# MCU.net
KiCad netlist of a schematic drawn in Altium Designer
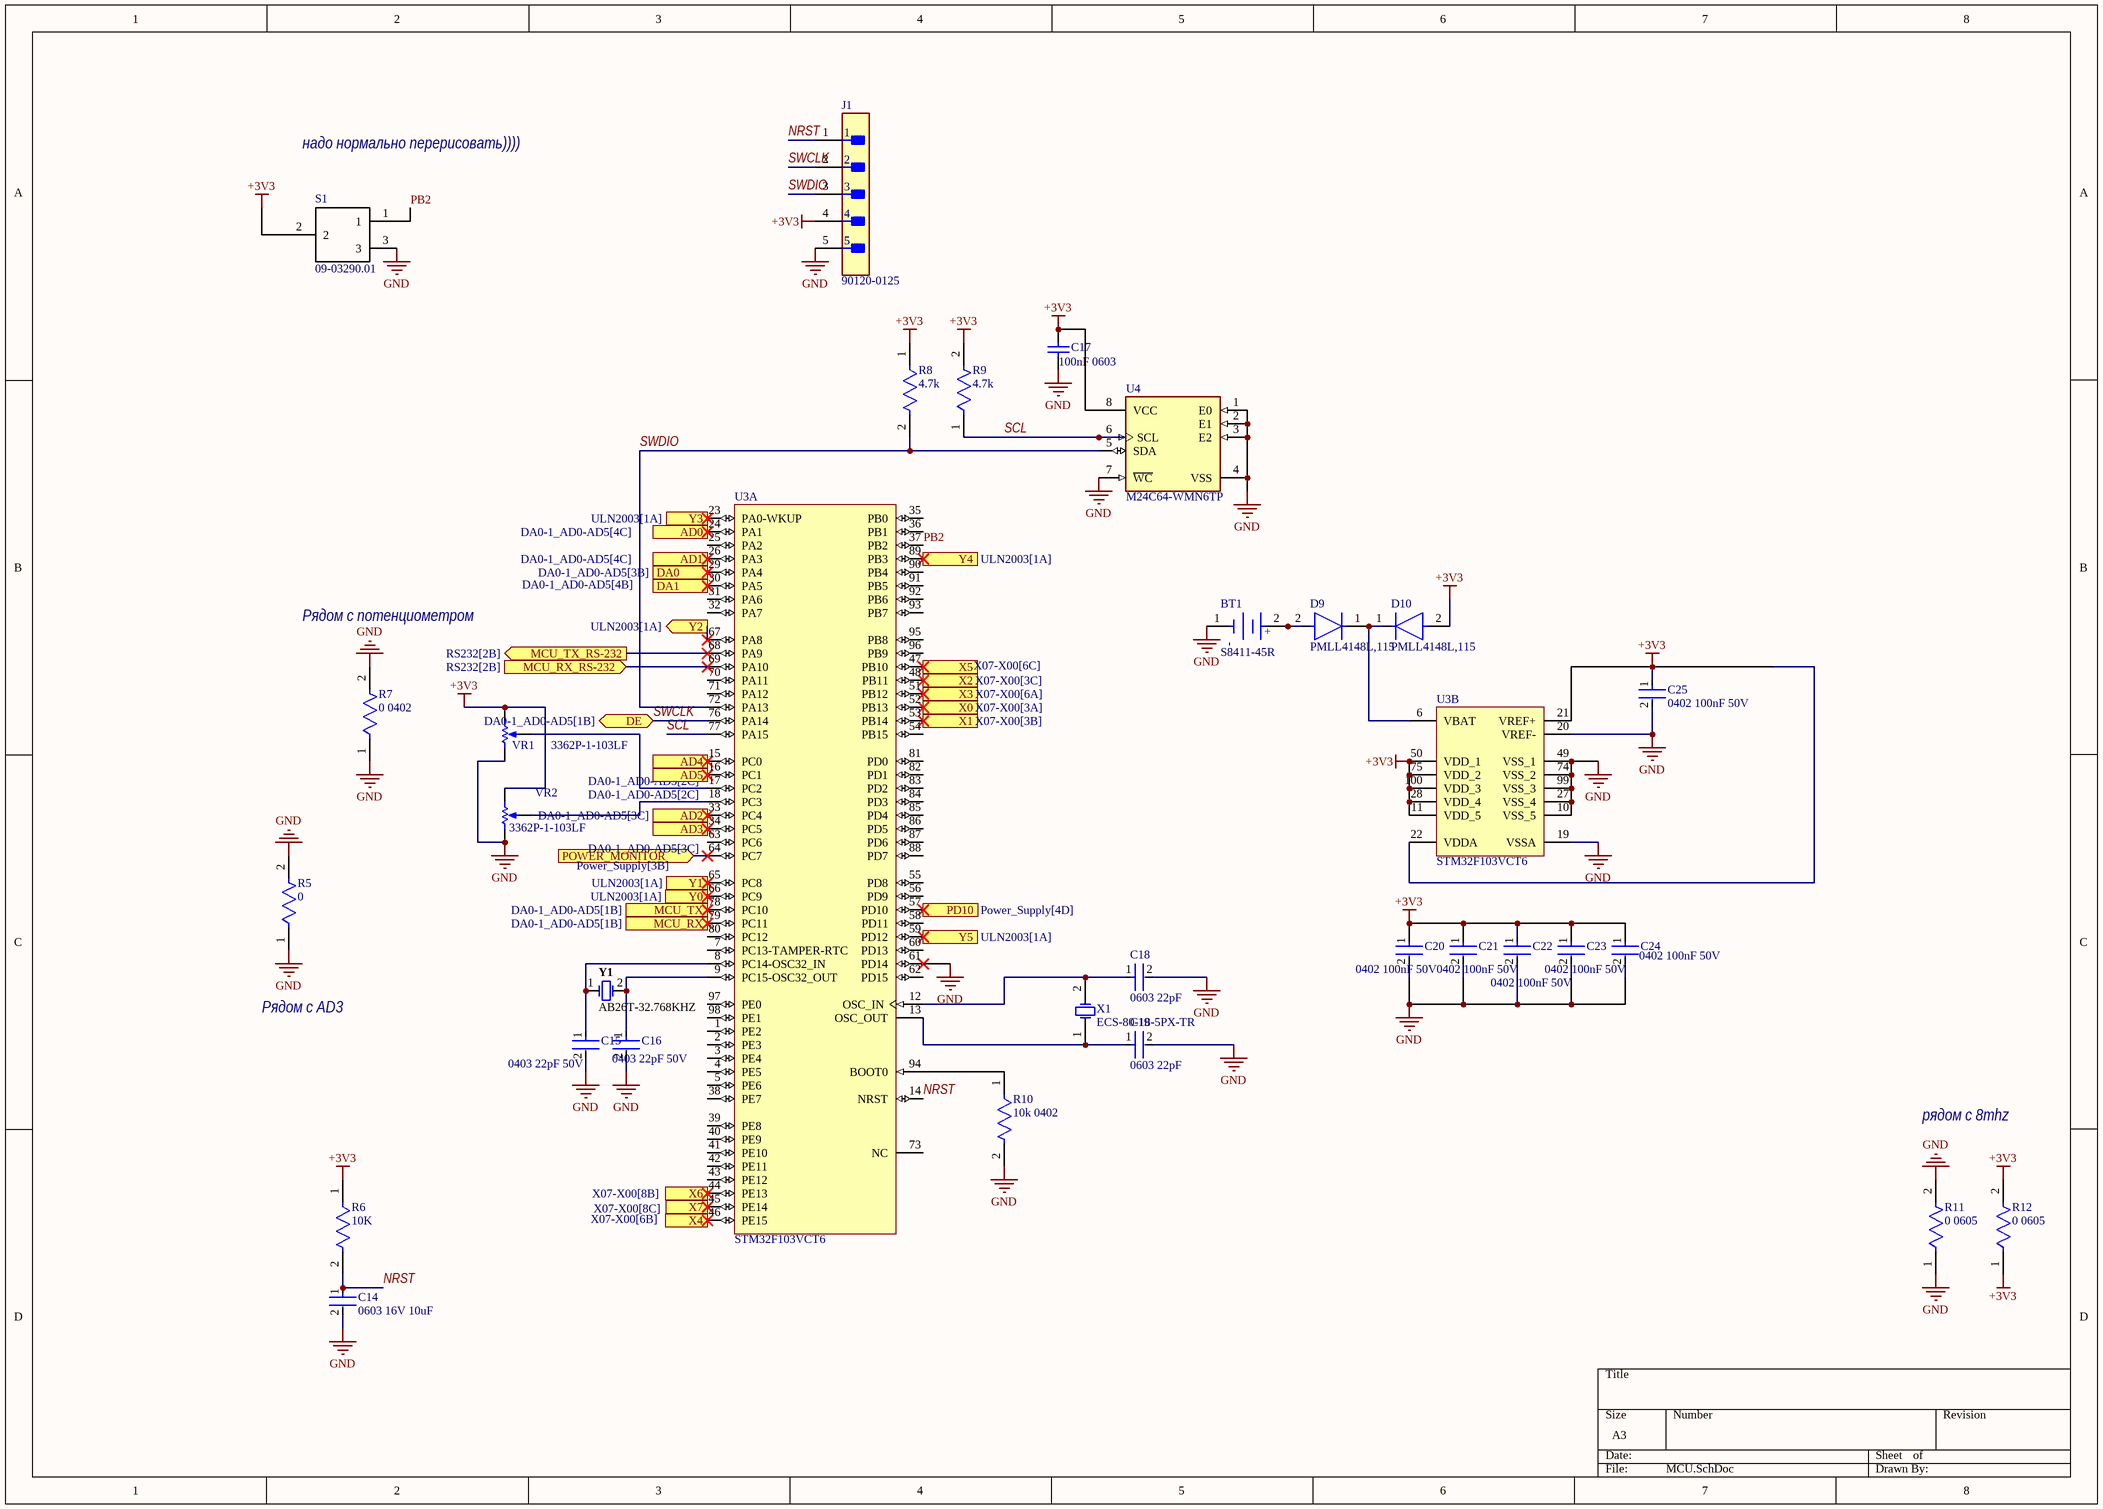
[diagram p0: MCU.SchDoc]

(export (version "E")
  (design (tool "Eeschema 10.0.6"))
  (components
    (comp (ref "BT1")
      (value "S8411-45R")
      (footprint "FP-S8411-45R-MFG")
      (description "BATTERY HOLDER COIN 12MM SMD")
      (libsource (lib "Altium Content Vault") (part "60d3b5b901a8747834971d0eb8cf3fd"))
    )
    (comp (ref "C14")
      (value "0603 16V 10uF")
      (footprint "FP-CC0603-DC-MFG")
      (description "CC0603KRX5R7BB106 Multilayer Ceramic Capacitor, 10 uF, 16 V, ± 10%, X5R, 0603 [1608 Metric]")
      (fields (field (name "TOLERANCE") "10%"))
      (libsource (lib "Altium Content Vault") (part "b4654b650e69147ec39a6b967a45e02"))
    )
    (comp (ref "C15")
      (value "0403 22pF 50V")
      (footprint "FP-C0402-BB-MFG")
      (description "C0402 22 pF C0G 5.00% 50 V")
      (fields (field (name "MANUFACTURER") "Kemet") (field (name "TOLERANCE") "0.05"))
      (libsource (lib "Altium Content Vault") (part "b4654b650e69147ec39a6b967a45e02"))
    )
    (comp (ref "C16")
      (value "0403 22pF 50V")
      (footprint "FP-C0402-BB-MFG")
      (description "C0402 22 pF C0G 5.00% 50 V")
      (fields (field (name "MANUFACTURER") "Kemet") (field (name "TOLERANCE") "0.05"))
      (libsource (lib "Altium Content Vault") (part "b4654b650e69147ec39a6b967a45e02"))
    )
    (comp (ref "C17")
      (value "100nF 0603")
      (footprint "CAPC1608X90X35LL15T15")
      (fields
        (field (name "MANUFACTURER") "AVX Interconnect / Elco")
        (field (name "PART NUMBER") "06035C104KAZ2A")
      )
      (libsource (lib "Altium Content Vault") (part "CAP"))
    )
    (comp (ref "C18")
      (value "0603 22pF")
      (footprint "FP-C0603C-CF-MFG")
      (description "C0603 22 pF X7R 30ppm/°C 5.00% 50 V")
      (fields
        (field (name "MANUFACTURER") "KEMET")
        (field (name "OCTOPART") "https://octopart.com/c0603c220j5ractu-kemet-47052364")
      )
      (libsource (lib "Altium Content Vault") (part "b4654b650e69147ec39a6b967a45e02"))
    )
    (comp (ref "C19")
      (value "0603 22pF")
      (footprint "FP-C0603C-CF-MFG")
      (description "C0603 22 pF X7R 30ppm/°C 5.00% 50 V")
      (fields
        (field (name "MANUFACTURER") "KEMET")
        (field (name "OCTOPART") "https://octopart.com/c0603c220j5ractu-kemet-47052364")
      )
      (libsource (lib "Altium Content Vault") (part "b4654b650e69147ec39a6b967a45e02"))
    )
    (comp (ref "C20")
      (value "0402 100nF 50V")
      (footprint "FP-0402B104K500CT-IPC_C")
      (description "CAP CER 0.1UF 50V X7R 0402")
      (fields (field (name "TOLERANCE") "10%"))
      (libsource (lib "Altium Content Vault") (part "11868f565c42a9108669ba33697ecf6"))
    )
    (comp (ref "C21")
      (value "0402 100nF 50V")
      (footprint "FP-0402B104K500CT-IPC_C")
      (description "CAP CER 0.1UF 50V X7R 0402")
      (fields (field (name "TOLERANCE") "10%"))
      (libsource (lib "Altium Content Vault") (part "11868f565c42a9108669ba33697ecf6"))
    )
    (comp (ref "C22")
      (value "0402 100nF 50V")
      (footprint "FP-0402B104K500CT-IPC_C")
      (description "CAP CER 0.1UF 50V X7R 0402")
      (fields (field (name "TOLERANCE") "10%"))
      (libsource (lib "Altium Content Vault") (part "11868f565c42a9108669ba33697ecf6"))
    )
    (comp (ref "C23")
      (value "0402 100nF 50V")
      (footprint "FP-0402B104K500CT-IPC_C")
      (description "CAP CER 0.1UF 50V X7R 0402")
      (fields (field (name "TOLERANCE") "10%"))
      (libsource (lib "Altium Content Vault") (part "11868f565c42a9108669ba33697ecf6"))
    )
    (comp (ref "C24")
      (value "0402 100nF 50V")
      (footprint "FP-0402B104K500CT-IPC_C")
      (description "CAP CER 0.1UF 50V X7R 0402")
      (fields (field (name "TOLERANCE") "10%"))
      (libsource (lib "Altium Content Vault") (part "11868f565c42a9108669ba33697ecf6"))
    )
    (comp (ref "C25")
      (value "0402 100nF 50V")
      (footprint "FP-0402B104K500CT-IPC_C")
      (description "CAP CER 0.1UF 50V X7R 0402")
      (fields (field (name "TOLERANCE") "10%"))
      (libsource (lib "Altium Content Vault") (part "11868f565c42a9108669ba33697ecf6"))
    )
    (comp (ref "D9")
      (value "PMLL4148L,115")
      (footprint "FP-SOD80C-MFG")
      (description "DIODE GEN PURP 75V 200MA LLDS")
      (fields
        (field (name "OCTOPART") "https://octopart.com/pmll4148l%2C115-nexperia-78741557")
        (field (name "MANUFACTURER") "Nexperia")
      )
      (libsource (lib "Altium Content Vault") (part "d7152d700b627762746794eb795d46e"))
    )
    (comp (ref "D10")
      (value "PMLL4148L,115")
      (footprint "FP-SOD80C-MFG")
      (description "DIODE GEN PURP 75V 200MA LLDS")
      (fields
        (field (name "OCTOPART") "https://octopart.com/pmll4148l%2C115-nexperia-78741557")
        (field (name "MANUFACTURER") "Nexperia")
      )
      (libsource (lib "Altium Content Vault") (part "d7152d700b627762746794eb795d46e"))
    )
    (comp (ref "J1")
      (value "90120-0125")
      (footprint "FP-90120-0125-MFG")
      (description "90120-0125 2.54mm Pitch C-Grid III Header, Single Row, Vertical, 5 Circuits, Tin (Sn) Plating")
      (libsource (lib "Altium Content Vault") (part "bf93c07fd2649a848d0ec8585582aab"))
    )
    (comp (ref "R5")
      (value "0")
      (footprint "FP-RCS0603-e3-MFG")
      (description "RES SMD 0 OHM JUMPER 1/4W 0603")
      (libsource (lib "Altium Content Vault") (part "1029c3af85768c4190bb7ad29bc67b5"))
    )
    (comp (ref "R6")
      (value "10K")
      (footprint "FP-RT0603-MFG")
      (description "RES SMD 10K OHM 0.05% 1/10W 0603")
      (fields
        (field (name "OCTOPART") "https://octopart.com/rt0603wre0710kl-yageo-71396825")
        (field (name "MANUFACTURER") "Yageo")
      )
      (libsource (lib "Altium Content Vault") (part "1029c3af85768c4190bb7ad29bc67b5"))
    )
    (comp (ref "R7")
      (value "0 0402")
      (footprint "FP-PMR01-MFG")
      (description "RES SMD 0 OHM JUMPER 1/5W 0402")
      (libsource (lib "Altium Content Vault") (part "1029c3af85768c4190bb7ad29bc67b5"))
    )
    (comp (ref "R8")
      (value "4.7k")
      (footprint "FP-TFCR0402-IPC_A")
      (description "RES Thin Film,  4.7kΩ, 0.5%, 0.063W, 25ppm/°C, 0402")
      (libsource (lib "Altium Content Vault") (part "1029c3af85768c4190bb7ad29bc67b5"))
    )
    (comp (ref "R9")
      (value "4.7k")
      (footprint "FP-TFCR0402-IPC_A")
      (description "RES Thin Film,  4.7kΩ, 0.5%, 0.063W, 25ppm/°C, 0402")
      (libsource (lib "Altium Content Vault") (part "1029c3af85768c4190bb7ad29bc67b5"))
    )
    (comp (ref "R10")
      (value "10k 0402")
      (footprint "FP-MCS0402-MFG")
      (description "RES SMD 1.2K OHM 1% 1/10W 0402")
      (fields (field (name "TOLERANCE") "0.5%"))
      (libsource (lib "Altium Content Vault") (part "1029c3af85768c4190bb7ad29bc67b5"))
    )
    (comp (ref "R11")
      (value "0 0605")
      (footprint "FP-HCJ0603-MFG")
      (description "RES 0 OHM JUMPER 1/4W 0603")
      (libsource (lib "Altium Content Vault") (part "1029c3af85768c4190bb7ad29bc67b5"))
    )
    (comp (ref "R12")
      (value "0 0605")
      (footprint "FP-HCJ0603-MFG")
      (description "RES 0 OHM JUMPER 1/4W 0603")
      (libsource (lib "Altium Content Vault") (part "1029c3af85768c4190bb7ad29bc67b5"))
    )
    (comp (ref "S1")
      (value "09-03290.01")
      (footprint "09.03290.01")
      (description "Switch")
      (libsource (lib "Schlib1") (part "09-03290.01"))
    )
    (comp (ref "U3")
      (value "STM32F103VCT6")
      (footprint "STM-LQFP100_L")
      (libsource (lib "Altium Content Vault") (part "MC-ARM-STM32F103XC_D_E-SQ100"))
    )
    (comp (ref "U4")
      (value "M24C64-WMN6TP")
      (footprint "FP-SO8N-SO-A-MFG")
      (description "IC EEPROM 64K I2C 1MHZ 8SO")
      (fields
        (field (name "OCTOPART") "https://octopart.com/m24c64-wmn6tp-stmicroelectronics-55412559")
        (field (name "MANUFACTURER") "STMicroelectronics")
      )
      (libsource (lib "Altium Content Vault") (part "3a9c539e3f9535f6888155586a46bbc"))
    )
    (comp (ref "VR1")
      (value "3362P-1-103LF")
      (footprint "BOUR-3362P")
      (description "Square Trimpot(R) Trimming Potentiometer, 10 KOhm, 300 V, -55 to 125 degC, 3-Pin THD, RoHS, Tube")
      (fields (field (name "TOLERANCE") "1%"))
      (libsource (lib "Altium Content Vault") (part "RES-POT-3"))
    )
    (comp (ref "VR2")
      (value "3362P-1-103LF")
      (footprint "BOUR-3362P")
      (description "Square Trimpot(R) Trimming Potentiometer, 10 KOhm, 300 V, -55 to 125 degC, 3-Pin THD, RoHS, Tube")
      (fields (field (name "TOLERANCE") "1%"))
      (libsource (lib "Altium Content Vault") (part "RES-POT-3"))
    )
    (comp (ref "X1")
      (value "ECS-80-18-5PX-TR")
      (footprint "ECS-80-18-5PX-TR_V")
      (description "Low Profile Quartz Crystal, 8.0 MHz, 2-Pin SMD, RoHS, Tape and Reel")
      (fields (field (name "TOLERANCE") "30PPM") (field (name "MANUFACTURER") "ECS"))
      (libsource (lib "Altium Content Vault") (part "XTAL_1-2-2"))
    )
    (comp (ref "Y1")
      (value "AB26T-32.768KHZ")
      (footprint "ABRA-AB26T")
      (description "Crystal, 12.5 pF, 32.768 KHz, -10 to 60 degC, 2-Pin THD, RoHS, Bulk")
      (fields (field (name "MANUFACTURER") "ABRACON") (field (name "TOLERANCE") "20PPM"))
      (libsource (lib "Altium Content Vault") (part "XTAL-1-2-2"))
    )
  )
  (nets
    (net (code "1") (name "+3V3") (class "Default")
      (node (ref "C17") (pin "2") (pinfunction "2_2") (pintype "passive"))
      (node (ref "C20") (pin "1") (pinfunction "1_1") (pintype "passive"))
      (node (ref "C21") (pin "1") (pinfunction "1_1") (pintype "passive"))
      (node (ref "C22") (pin "1") (pinfunction "1_1") (pintype "passive"))
      (node (ref "C23") (pin "1") (pinfunction "1_1") (pintype "passive"))
      (node (ref "C24") (pin "1") (pinfunction "1_1") (pintype "passive"))
      (node (ref "C25") (pin "1") (pinfunction "1_1") (pintype "passive"))
      (node (ref "D10") (pin "2") (pinfunction "A_2") (pintype "passive"))
      (node (ref "J1") (pin "4") (pinfunction "4_4") (pintype "passive"))
      (node (ref "R12") (pin "1") (pinfunction "1_1") (pintype "passive"))
      (node (ref "R12") (pin "2") (pinfunction "2_2") (pintype "passive"))
      (node (ref "R6") (pin "1") (pinfunction "1_1") (pintype "passive"))
      (node (ref "R8") (pin "1") (pinfunction "1_1") (pintype "passive"))
      (node (ref "R9") (pin "2") (pinfunction "2_2") (pintype "passive"))
      (node (ref "S1") (pin "2") (pinfunction "2_2") (pintype "passive"))
      (node (ref "U3") (pin "100") (pinfunction "VDD_3_100") (pintype "power_in"))
      (node (ref "U3") (pin "11") (pinfunction "VDD_5_11") (pintype "power_in"))
      (node (ref "U3") (pin "21") (pinfunction "VREF+_21") (pintype "power_in"))
      (node (ref "U3") (pin "22") (pinfunction "VDDA_22") (pintype "power_in"))
      (node (ref "U3") (pin "28") (pinfunction "VDD_4_28") (pintype "power_in"))
      (node (ref "U3") (pin "50") (pinfunction "VDD_1_50") (pintype "power_in"))
      (node (ref "U3") (pin "75") (pinfunction "VDD_2_75") (pintype "power_in"))
      (node (ref "U4") (pin "8") (pinfunction "VCC_8") (pintype "power_in"))
      (node (ref "VR1") (pin "3") (pinfunction "CW_3") (pintype "passive"))
      (node (ref "VR2") (pin "3") (pinfunction "CW_3") (pintype "passive"))
    )
    (net (code "2") (name "/AD0") (class "Default")
      (node (ref "U3") (pin "24") (pinfunction "PA1_24") (pintype "bidirectional+no_connect"))
    )
    (net (code "3") (name "/AD1") (class "Default")
      (node (ref "U3") (pin "26") (pinfunction "PA3_26") (pintype "bidirectional+no_connect"))
    )
    (net (code "4") (name "/AD2") (class "Default")
      (node (ref "U3") (pin "33") (pinfunction "PC4_33") (pintype "bidirectional+no_connect"))
    )
    (net (code "5") (name "/AD3") (class "Default")
      (node (ref "U3") (pin "34") (pinfunction "PC5_34") (pintype "bidirectional+no_connect"))
    )
    (net (code "6") (name "/AD4") (class "Default")
      (node (ref "U3") (pin "15") (pinfunction "PC0_15") (pintype "bidirectional+no_connect"))
    )
    (net (code "7") (name "/AD5") (class "Default")
      (node (ref "U3") (pin "16") (pinfunction "PC1_16") (pintype "bidirectional+no_connect"))
    )
    (net (code "8") (name "/DA0") (class "Default")
      (node (ref "U3") (pin "29") (pinfunction "PA4_29") (pintype "bidirectional+no_connect"))
    )
    (net (code "9") (name "/DA1") (class "Default")
      (node (ref "U3") (pin "30") (pinfunction "PA5_30") (pintype "bidirectional+no_connect"))
    )
    (net (code "10") (name "/MCU_RX") (class "Default")
      (node (ref "U3") (pin "79") (pinfunction "PC11_79") (pintype "bidirectional+no_connect"))
    )
    (net (code "11") (name "/MCU_RX_RS-232") (class "Default")
      (node (ref "U3") (pin "69") (pinfunction "PA10_69") (pintype "bidirectional+no_connect"))
    )
    (net (code "12") (name "/MCU_TX") (class "Default")
      (node (ref "U3") (pin "78") (pinfunction "PC10_78") (pintype "bidirectional+no_connect"))
    )
    (net (code "13") (name "/MCU_TX_RS-232") (class "Default")
      (node (ref "U3") (pin "68") (pinfunction "PA9_68") (pintype "bidirectional+no_connect"))
    )
    (net (code "14") (name "/NRST") (class "Default")
      (node (ref "C14") (pin "1") (pinfunction "1_1") (pintype "passive"))
      (node (ref "J1") (pin "1") (pinfunction "1_1") (pintype "passive"))
      (node (ref "R6") (pin "2") (pinfunction "2_2") (pintype "passive"))
      (node (ref "U3") (pin "14") (pinfunction "NRST_14") (pintype "bidirectional"))
    )
    (net (code "15") (name "/PB2") (class "Default")
      (node (ref "S1") (pin "1") (pinfunction "1_1") (pintype "passive"))
      (node (ref "U3") (pin "37") (pinfunction "PB2_37") (pintype "bidirectional"))
    )
    (net (code "16") (name "/PD10") (class "Default")
      (node (ref "U3") (pin "57") (pinfunction "PD10_57") (pintype "bidirectional+no_connect"))
    )
    (net (code "17") (name "/POWER_MONITOR") (class "Default")
      (node (ref "U3") (pin "64") (pinfunction "PC7_64") (pintype "bidirectional+no_connect"))
    )
    (net (code "18") (name "/SCL") (class "Default")
      (node (ref "R9") (pin "1") (pinfunction "1_1") (pintype "passive"))
      (node (ref "U3") (pin "77") (pinfunction "PA15_77") (pintype "bidirectional"))
      (node (ref "U4") (pin "6") (pinfunction "SCL_6") (pintype "input"))
    )
    (net (code "19") (name "/SWCLK") (class "Default")
      (node (ref "J1") (pin "2") (pinfunction "2_2") (pintype "passive"))
      (node (ref "U3") (pin "76") (pinfunction "PA14_76") (pintype "bidirectional"))
    )
    (net (code "20") (name "/SWDIO") (class "Default")
      (node (ref "J1") (pin "3") (pinfunction "3_3") (pintype "passive"))
      (node (ref "R8") (pin "2") (pinfunction "2_2") (pintype "passive"))
      (node (ref "U3") (pin "72") (pinfunction "PA13_72") (pintype "bidirectional"))
      (node (ref "U4") (pin "5") (pinfunction "SDA_5") (pintype "bidirectional"))
    )
    (net (code "21") (name "/X0") (class "Default")
      (node (ref "U3") (pin "52") (pinfunction "PB13_52") (pintype "bidirectional+no_connect"))
    )
    (net (code "22") (name "/X1") (class "Default")
      (node (ref "U3") (pin "53") (pinfunction "PB14_53") (pintype "bidirectional+no_connect"))
    )
    (net (code "23") (name "/X2") (class "Default")
      (node (ref "U3") (pin "48") (pinfunction "PB11_48") (pintype "bidirectional+no_connect"))
    )
    (net (code "24") (name "/X3") (class "Default")
      (node (ref "U3") (pin "51") (pinfunction "PB12_51") (pintype "bidirectional+no_connect"))
    )
    (net (code "25") (name "/X4") (class "Default")
      (node (ref "U3") (pin "46") (pinfunction "PE15_46") (pintype "bidirectional+no_connect"))
    )
    (net (code "26") (name "/X5") (class "Default")
      (node (ref "U3") (pin "47") (pinfunction "PB10_47") (pintype "bidirectional+no_connect"))
    )
    (net (code "27") (name "/X6") (class "Default")
      (node (ref "U3") (pin "44") (pinfunction "PE13_44") (pintype "bidirectional+no_connect"))
    )
    (net (code "28") (name "/X7") (class "Default")
      (node (ref "U3") (pin "45") (pinfunction "PE14_45") (pintype "bidirectional+no_connect"))
    )
    (net (code "29") (name "/Y0") (class "Default")
      (node (ref "U3") (pin "66") (pinfunction "PC9_66") (pintype "bidirectional+no_connect"))
    )
    (net (code "30") (name "/Y1") (class "Default")
      (node (ref "U3") (pin "65") (pinfunction "PC8_65") (pintype "bidirectional+no_connect"))
    )
    (net (code "31") (name "/Y2") (class "Default")
      (node (ref "U3") (pin "67") (pinfunction "PA8_67") (pintype "bidirectional+no_connect"))
    )
    (net (code "32") (name "/Y3") (class "Default")
      (node (ref "U3") (pin "23") (pinfunction "PA0-WKUP_23") (pintype "bidirectional+no_connect"))
    )
    (net (code "33") (name "/Y4") (class "Default")
      (node (ref "U3") (pin "89") (pinfunction "PB3_89") (pintype "bidirectional+no_connect"))
    )
    (net (code "34") (name "/Y5") (class "Default")
      (node (ref "U3") (pin "59") (pinfunction "PD12_59") (pintype "bidirectional+no_connect"))
    )
    (net (code "35") (name "GND") (class "Default")
      (node (ref "BT1") (pin "1") (pinfunction "C_1") (pintype "passive"))
      (node (ref "C14") (pin "2") (pinfunction "2_2") (pintype "passive"))
      (node (ref "C15") (pin "2") (pinfunction "2_2") (pintype "passive"))
      (node (ref "C16") (pin "2") (pinfunction "2_2") (pintype "passive"))
      (node (ref "C17") (pin "1") (pinfunction "1_1") (pintype "passive"))
      (node (ref "C18") (pin "2") (pinfunction "2_2") (pintype "passive"))
      (node (ref "C19") (pin "2") (pinfunction "2_2") (pintype "passive"))
      (node (ref "C20") (pin "2") (pinfunction "2_2") (pintype "passive"))
      (node (ref "C21") (pin "2") (pinfunction "2_2") (pintype "passive"))
      (node (ref "C22") (pin "2") (pinfunction "2_2") (pintype "passive"))
      (node (ref "C23") (pin "2") (pinfunction "2_2") (pintype "passive"))
      (node (ref "C24") (pin "2") (pinfunction "2_2") (pintype "passive"))
      (node (ref "C25") (pin "2") (pinfunction "2_2") (pintype "passive"))
      (node (ref "J1") (pin "5") (pinfunction "5_5") (pintype "passive"))
      (node (ref "R10") (pin "2") (pinfunction "2_2") (pintype "passive"))
      (node (ref "R11") (pin "1") (pinfunction "1_1") (pintype "passive"))
      (node (ref "R11") (pin "2") (pinfunction "2_2") (pintype "passive"))
      (node (ref "R5") (pin "1") (pinfunction "1_1") (pintype "passive"))
      (node (ref "R5") (pin "2") (pinfunction "2_2") (pintype "passive"))
      (node (ref "R7") (pin "1") (pinfunction "1_1") (pintype "passive"))
      (node (ref "R7") (pin "2") (pinfunction "2_2") (pintype "passive"))
      (node (ref "S1") (pin "3") (pinfunction "3_3") (pintype "passive"))
      (node (ref "U3") (pin "10") (pinfunction "VSS_5_10") (pintype "power_in"))
      (node (ref "U3") (pin "19") (pinfunction "VSSA_19") (pintype "power_in"))
      (node (ref "U3") (pin "20") (pinfunction "VREF-_20") (pintype "power_in"))
      (node (ref "U3") (pin "27") (pinfunction "VSS_4_27") (pintype "power_in"))
      (node (ref "U3") (pin "49") (pinfunction "VSS_1_49") (pintype "power_in"))
      (node (ref "U3") (pin "61") (pinfunction "PD14_61") (pintype "bidirectional"))
      (node (ref "U3") (pin "74") (pinfunction "VSS_2_74") (pintype "power_in"))
      (node (ref "U3") (pin "99") (pinfunction "VSS_3_99") (pintype "power_in"))
      (node (ref "U4") (pin "1") (pinfunction "E0_1") (pintype "input"))
      (node (ref "U4") (pin "2") (pinfunction "E1_2") (pintype "input"))
      (node (ref "U4") (pin "3") (pinfunction "E2_3") (pintype "input"))
      (node (ref "U4") (pin "4") (pinfunction "VSS_4") (pintype "power_in"))
      (node (ref "U4") (pin "7") (pinfunction "~{WC}_7") (pintype "input"))
      (node (ref "VR1") (pin "1") (pinfunction "CCW_1") (pintype "passive"))
      (node (ref "VR2") (pin "1") (pinfunction "CCW_1") (pintype "passive"))
    )
    (net (code "36") (name "Net-(BT1-A)") (class "Default")
      (node (ref "BT1") (pin "2") (pinfunction "A_2") (pintype "passive"))
      (node (ref "D9") (pin "2") (pinfunction "A_2") (pintype "passive"))
    )
    (net (code "37") (name "Net-(D10-C)") (class "Default")
      (node (ref "D10") (pin "1") (pinfunction "C_1") (pintype "passive"))
      (node (ref "D9") (pin "1") (pinfunction "C_1") (pintype "passive"))
      (node (ref "U3") (pin "6") (pinfunction "VBAT_6") (pintype "power_in"))
    )
    (net (code "38") (name "Net-(U3A-BOOT0)") (class "Default")
      (node (ref "R10") (pin "1") (pinfunction "1_1") (pintype "passive"))
      (node (ref "U3") (pin "94") (pinfunction "BOOT0_94") (pintype "input"))
    )
    (net (code "39") (name "Net-(U3A-OSC_IN)") (class "Default")
      (node (ref "C18") (pin "1") (pinfunction "1_1") (pintype "passive"))
      (node (ref "U3") (pin "12") (pinfunction "OSC_IN_12") (pintype "input"))
      (node (ref "X1") (pin "2") (pinfunction "X2_2") (pintype "passive"))
    )
    (net (code "40") (name "Net-(U3A-OSC_OUT)") (class "Default")
      (node (ref "C19") (pin "1") (pinfunction "1_1") (pintype "passive"))
      (node (ref "U3") (pin "13") (pinfunction "OSC_OUT_13") (pintype "passive"))
      (node (ref "X1") (pin "1") (pinfunction "X1_1") (pintype "passive"))
    )
    (net (code "41") (name "Net-(U3A-PC2)") (class "Default")
      (node (ref "U3") (pin "17") (pinfunction "PC2_17") (pintype "bidirectional"))
      (node (ref "VR1") (pin "2") (pinfunction "S_2") (pintype "passive"))
    )
    (net (code "42") (name "Net-(U3A-PC3)") (class "Default")
      (node (ref "U3") (pin "18") (pinfunction "PC3_18") (pintype "bidirectional"))
      (node (ref "VR2") (pin "2") (pinfunction "S_2") (pintype "passive"))
    )
    (net (code "43") (name "Net-(U3A-PC14-OSC32_IN)") (class "Default")
      (node (ref "C15") (pin "1") (pinfunction "1_1") (pintype "passive"))
      (node (ref "U3") (pin "8") (pinfunction "PC14-OSC32_IN_8") (pintype "bidirectional"))
      (node (ref "Y1") (pin "1") (pinfunction "1_1") (pintype "passive"))
    )
    (net (code "44") (name "Net-(U3A-PC15-OSC32_OUT)") (class "Default")
      (node (ref "C16") (pin "1") (pinfunction "1_1") (pintype "passive"))
      (node (ref "U3") (pin "9") (pinfunction "PC15-OSC32_OUT_9") (pintype "bidirectional"))
      (node (ref "Y1") (pin "2") (pinfunction "2_2") (pintype "passive"))
    )
    (net (code "45") (name "unconnected-(U3A-NC-Pad73)") (class "Default")
      (node (ref "U3") (pin "73") (pinfunction "NC_73") (pintype "passive"))
    )
    (net (code "46") (name "unconnected-(U3A-PA2-Pad25)") (class "Default")
      (node (ref "U3") (pin "25") (pinfunction "PA2_25") (pintype "bidirectional"))
    )
    (net (code "47") (name "unconnected-(U3A-PA6-Pad31)") (class "Default")
      (node (ref "U3") (pin "31") (pinfunction "PA6_31") (pintype "bidirectional"))
    )
    (net (code "48") (name "unconnected-(U3A-PA7-Pad32)") (class "Default")
      (node (ref "U3") (pin "32") (pinfunction "PA7_32") (pintype "bidirectional"))
    )
    (net (code "49") (name "unconnected-(U3A-PA11-Pad70)") (class "Default")
      (node (ref "U3") (pin "70") (pinfunction "PA11_70") (pintype "bidirectional"))
    )
    (net (code "50") (name "unconnected-(U3A-PA12-Pad71)") (class "Default")
      (node (ref "U3") (pin "71") (pinfunction "PA12_71") (pintype "bidirectional"))
    )
    (net (code "51") (name "unconnected-(U3A-PB0-Pad35)") (class "Default")
      (node (ref "U3") (pin "35") (pinfunction "PB0_35") (pintype "bidirectional"))
    )
    (net (code "52") (name "unconnected-(U3A-PB1-Pad36)") (class "Default")
      (node (ref "U3") (pin "36") (pinfunction "PB1_36") (pintype "bidirectional"))
    )
    (net (code "53") (name "unconnected-(U3A-PB4-Pad90)") (class "Default")
      (node (ref "U3") (pin "90") (pinfunction "PB4_90") (pintype "bidirectional"))
    )
    (net (code "54") (name "unconnected-(U3A-PB5-Pad91)") (class "Default")
      (node (ref "U3") (pin "91") (pinfunction "PB5_91") (pintype "bidirectional"))
    )
    (net (code "55") (name "unconnected-(U3A-PB6-Pad92)") (class "Default")
      (node (ref "U3") (pin "92") (pinfunction "PB6_92") (pintype "bidirectional"))
    )
    (net (code "56") (name "unconnected-(U3A-PB7-Pad93)") (class "Default")
      (node (ref "U3") (pin "93") (pinfunction "PB7_93") (pintype "bidirectional"))
    )
    (net (code "57") (name "unconnected-(U3A-PB8-Pad95)") (class "Default")
      (node (ref "U3") (pin "95") (pinfunction "PB8_95") (pintype "bidirectional"))
    )
    (net (code "58") (name "unconnected-(U3A-PB9-Pad96)") (class "Default")
      (node (ref "U3") (pin "96") (pinfunction "PB9_96") (pintype "bidirectional"))
    )
    (net (code "59") (name "unconnected-(U3A-PB15-Pad54)") (class "Default")
      (node (ref "U3") (pin "54") (pinfunction "PB15_54") (pintype "bidirectional"))
    )
    (net (code "60") (name "unconnected-(U3A-PC6-Pad63)") (class "Default")
      (node (ref "U3") (pin "63") (pinfunction "PC6_63") (pintype "bidirectional"))
    )
    (net (code "61") (name "unconnected-(U3A-PC12-Pad80)") (class "Default")
      (node (ref "U3") (pin "80") (pinfunction "PC12_80") (pintype "bidirectional"))
    )
    (net (code "62") (name "unconnected-(U3A-PC13-TAMPER-RTC-Pad7)") (class "Default")
      (node (ref "U3") (pin "7") (pinfunction "PC13-TAMPER-RTC_7") (pintype "bidirectional"))
    )
    (net (code "63") (name "unconnected-(U3A-PD0-Pad81)") (class "Default")
      (node (ref "U3") (pin "81") (pinfunction "PD0_81") (pintype "bidirectional"))
    )
    (net (code "64") (name "unconnected-(U3A-PD1-Pad82)") (class "Default")
      (node (ref "U3") (pin "82") (pinfunction "PD1_82") (pintype "bidirectional"))
    )
    (net (code "65") (name "unconnected-(U3A-PD2-Pad83)") (class "Default")
      (node (ref "U3") (pin "83") (pinfunction "PD2_83") (pintype "bidirectional"))
    )
    (net (code "66") (name "unconnected-(U3A-PD3-Pad84)") (class "Default")
      (node (ref "U3") (pin "84") (pinfunction "PD3_84") (pintype "bidirectional"))
    )
    (net (code "67") (name "unconnected-(U3A-PD4-Pad85)") (class "Default")
      (node (ref "U3") (pin "85") (pinfunction "PD4_85") (pintype "bidirectional"))
    )
    (net (code "68") (name "unconnected-(U3A-PD5-Pad86)") (class "Default")
      (node (ref "U3") (pin "86") (pinfunction "PD5_86") (pintype "bidirectional"))
    )
    (net (code "69") (name "unconnected-(U3A-PD6-Pad87)") (class "Default")
      (node (ref "U3") (pin "87") (pinfunction "PD6_87") (pintype "bidirectional"))
    )
    (net (code "70") (name "unconnected-(U3A-PD7-Pad88)") (class "Default")
      (node (ref "U3") (pin "88") (pinfunction "PD7_88") (pintype "bidirectional"))
    )
    (net (code "71") (name "unconnected-(U3A-PD8-Pad55)") (class "Default")
      (node (ref "U3") (pin "55") (pinfunction "PD8_55") (pintype "bidirectional"))
    )
    (net (code "72") (name "unconnected-(U3A-PD9-Pad56)") (class "Default")
      (node (ref "U3") (pin "56") (pinfunction "PD9_56") (pintype "bidirectional"))
    )
    (net (code "73") (name "unconnected-(U3A-PD11-Pad58)") (class "Default")
      (node (ref "U3") (pin "58") (pinfunction "PD11_58") (pintype "bidirectional"))
    )
    (net (code "74") (name "unconnected-(U3A-PD13-Pad60)") (class "Default")
      (node (ref "U3") (pin "60") (pinfunction "PD13_60") (pintype "bidirectional"))
    )
    (net (code "75") (name "unconnected-(U3A-PD15-Pad62)") (class "Default")
      (node (ref "U3") (pin "62") (pinfunction "PD15_62") (pintype "bidirectional"))
    )
    (net (code "76") (name "unconnected-(U3A-PE0-Pad97)") (class "Default")
      (node (ref "U3") (pin "97") (pinfunction "PE0_97") (pintype "bidirectional"))
    )
    (net (code "77") (name "unconnected-(U3A-PE1-Pad98)") (class "Default")
      (node (ref "U3") (pin "98") (pinfunction "PE1_98") (pintype "bidirectional"))
    )
    (net (code "78") (name "unconnected-(U3A-PE2-Pad1)") (class "Default")
      (node (ref "U3") (pin "1") (pinfunction "PE2_1") (pintype "bidirectional"))
    )
    (net (code "79") (name "unconnected-(U3A-PE3-Pad2)") (class "Default")
      (node (ref "U3") (pin "2") (pinfunction "PE3_2") (pintype "bidirectional"))
    )
    (net (code "80") (name "unconnected-(U3A-PE4-Pad3)") (class "Default")
      (node (ref "U3") (pin "3") (pinfunction "PE4_3") (pintype "bidirectional"))
    )
    (net (code "81") (name "unconnected-(U3A-PE5-Pad4)") (class "Default")
      (node (ref "U3") (pin "4") (pinfunction "PE5_4") (pintype "bidirectional"))
    )
    (net (code "82") (name "unconnected-(U3A-PE6-Pad5)") (class "Default")
      (node (ref "U3") (pin "5") (pinfunction "PE6_5") (pintype "bidirectional"))
    )
    (net (code "83") (name "unconnected-(U3A-PE7-Pad38)") (class "Default")
      (node (ref "U3") (pin "38") (pinfunction "PE7_38") (pintype "bidirectional"))
    )
    (net (code "84") (name "unconnected-(U3A-PE8-Pad39)") (class "Default")
      (node (ref "U3") (pin "39") (pinfunction "PE8_39") (pintype "bidirectional"))
    )
    (net (code "85") (name "unconnected-(U3A-PE9-Pad40)") (class "Default")
      (node (ref "U3") (pin "40") (pinfunction "PE9_40") (pintype "bidirectional"))
    )
    (net (code "86") (name "unconnected-(U3A-PE10-Pad41)") (class "Default")
      (node (ref "U3") (pin "41") (pinfunction "PE10_41") (pintype "bidirectional"))
    )
    (net (code "87") (name "unconnected-(U3A-PE11-Pad42)") (class "Default")
      (node (ref "U3") (pin "42") (pinfunction "PE11_42") (pintype "bidirectional"))
    )
    (net (code "88") (name "unconnected-(U3A-PE12-Pad43)") (class "Default")
      (node (ref "U3") (pin "43") (pinfunction "PE12_43") (pintype "bidirectional"))
    )
  )
)
